# Sheet1.net
KiCad netlist of a schematic drawn in Altium Designer
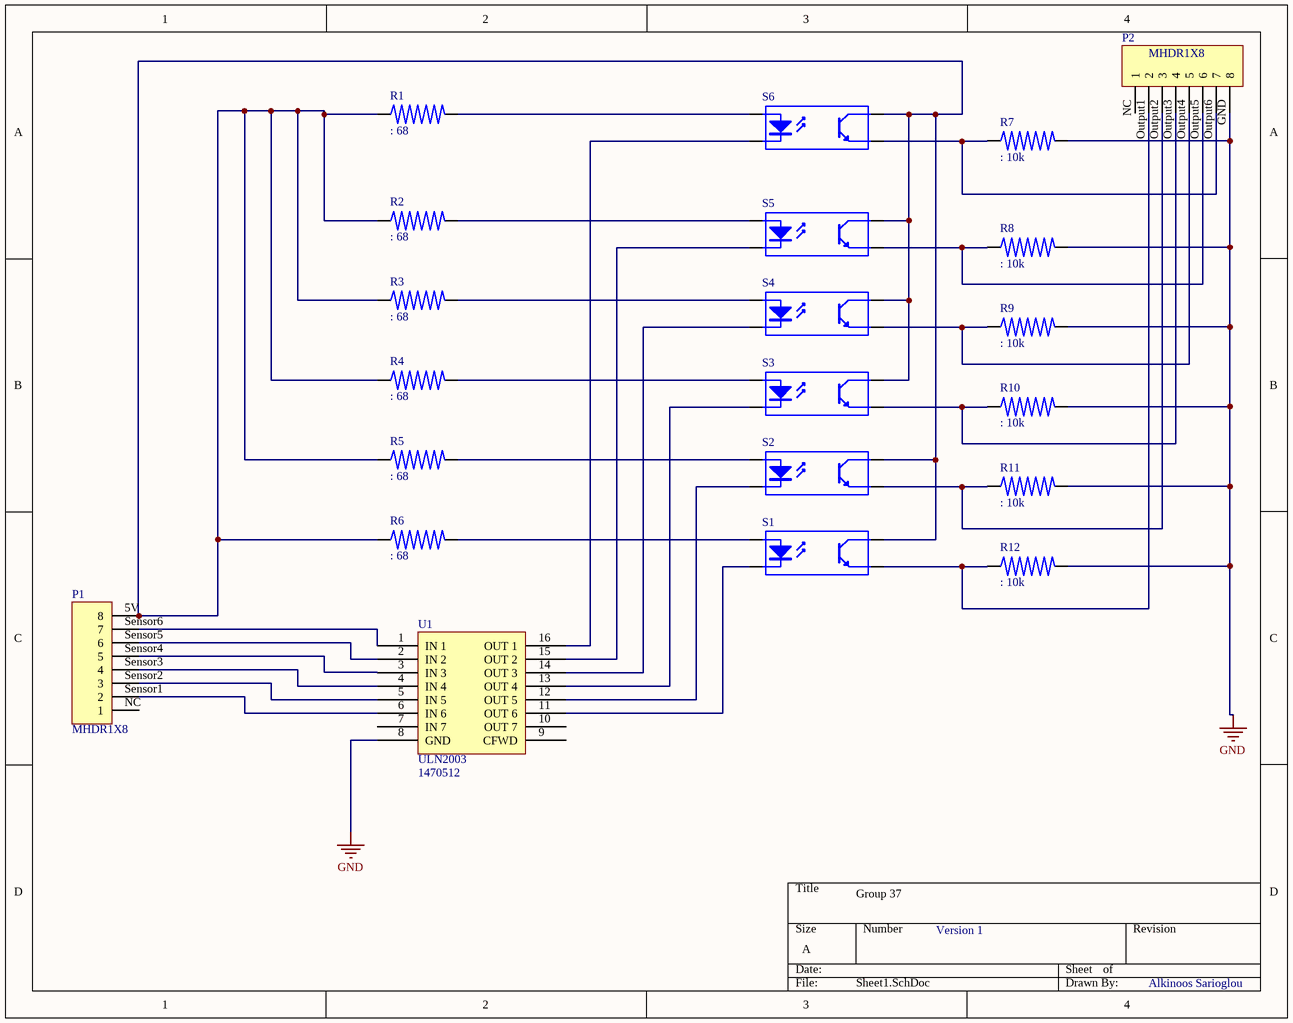
[diagram p0: Sheet1.SchDoc]

(export (version "E")
  (design (tool "Eeschema 10.0.6"))
  (components
    (comp (ref "P1")
      (value "MHDR1X8")
      (footprint "MHDR1X8")
      (description "Header, 8-Pin")
      (fields (field (name "PUBLISHER") "Altium Limited"))
      (libsource (lib "") (part "MHDR1X8_1"))
    )
    (comp (ref "P2")
      (value "MHDR1X8")
      (footprint "MHDR1X8")
      (description "Header, 8-Pin")
      (fields (field (name "PUBLISHER") "Altium Limited"))
      (libsource (lib "Miscellaneous Connectors") (part "MHDR1X8"))
    )
    (comp (ref "R1")
      (value "Resistor (IO board)")
      (footprint "RESISTOR_10K_TH_QW")
      (description "Resistor (SFR25)")
      (fields (field (name "ALTIUM_UNNAMED_1") "68"))
      (libsource (lib "Integrated_Library") (part "Resistor(IO board)"))
    )
    (comp (ref "R2")
      (value "Resistor (IO board)")
      (footprint "RESISTOR_10K_TH_QW")
      (description "Resistor (SFR25)")
      (fields (field (name "ALTIUM_UNNAMED_1") "68"))
      (libsource (lib "Integrated_Library") (part "Resistor(IO board)"))
    )
    (comp (ref "R3")
      (value "Resistor (IO board)")
      (footprint "RESISTOR_10K_TH_QW")
      (description "Resistor (SFR25)")
      (fields (field (name "ALTIUM_UNNAMED_1") "68"))
      (libsource (lib "Integrated_Library") (part "Resistor(IO board)"))
    )
    (comp (ref "R4")
      (value "Resistor (IO board)")
      (footprint "RESISTOR_10K_TH_QW")
      (description "Resistor (SFR25)")
      (fields (field (name "ALTIUM_UNNAMED_1") "68"))
      (libsource (lib "Integrated_Library") (part "Resistor(IO board)"))
    )
    (comp (ref "R5")
      (value "Resistor (IO board)")
      (footprint "RESISTOR_10K_TH_QW")
      (description "Resistor (SFR25)")
      (fields (field (name "ALTIUM_UNNAMED_1") "68"))
      (libsource (lib "Integrated_Library") (part "Resistor(IO board)"))
    )
    (comp (ref "R6")
      (value "Resistor (IO board)")
      (footprint "RESISTOR_10K_TH_QW")
      (description "Resistor (SFR25)")
      (fields (field (name "ALTIUM_UNNAMED_1") "68"))
      (libsource (lib "Integrated_Library") (part "Resistor(IO board)"))
    )
    (comp (ref "R7")
      (value "Resistor (IO board)")
      (footprint "RESISTOR_10K_TH_QW")
      (description "Resistor (SFR25)")
      (fields (field (name "ALTIUM_UNNAMED_1") "10k"))
      (libsource (lib "Integrated_Library") (part "Resistor(IO board)"))
    )
    (comp (ref "R8")
      (value "Resistor (IO board)")
      (footprint "RESISTOR_10K_TH_QW")
      (description "Resistor (SFR25)")
      (fields (field (name "ALTIUM_UNNAMED_1") "10k"))
      (libsource (lib "Integrated_Library") (part "Resistor(IO board)"))
    )
    (comp (ref "R9")
      (value "Resistor (IO board)")
      (footprint "RESISTOR_10K_TH_QW")
      (description "Resistor (SFR25)")
      (fields (field (name "ALTIUM_UNNAMED_1") "10k"))
      (libsource (lib "Integrated_Library") (part "Resistor(IO board)"))
    )
    (comp (ref "R10")
      (value "Resistor (IO board)")
      (footprint "RESISTOR_10K_TH_QW")
      (description "Resistor (SFR25)")
      (fields (field (name "ALTIUM_UNNAMED_1") "10k"))
      (libsource (lib "Integrated_Library") (part "Resistor(IO board)"))
    )
    (comp (ref "R11")
      (value "Resistor (IO board)")
      (footprint "RESISTOR_10K_TH_QW")
      (description "Resistor (SFR25)")
      (fields (field (name "ALTIUM_UNNAMED_1") "10k"))
      (libsource (lib "Integrated_Library") (part "Resistor(IO board)"))
    )
    (comp (ref "R12")
      (value "Resistor (IO board)")
      (footprint "RESISTOR_10K_TH_QW")
      (description "Resistor (SFR25)")
      (fields (field (name "ALTIUM_UNNAMED_1") "10k"))
      (libsource (lib "Integrated_Library") (part "Resistor(IO board)"))
    )
    (comp (ref "S1")
      (value "TCRT5000(On PCB)")
      (footprint "TCRT5000 Breakout")
      (description "4-Pin Phototransistor Optocoupler")
      (fields (field (name "PUBLISHER") "Altium Limited"))
      (libsource (lib "Integrated_Library") (part "TCRT5000(On PCB)"))
    )
    (comp (ref "S2")
      (value "TCRT5000(On PCB)")
      (footprint "TCRT5000 Breakout")
      (description "4-Pin Phototransistor Optocoupler")
      (fields (field (name "PUBLISHER") "Altium Limited"))
      (libsource (lib "Integrated_Library") (part "TCRT5000(On PCB)"))
    )
    (comp (ref "S3")
      (value "TCRT5000(On PCB)")
      (footprint "TCRT5000 Breakout")
      (description "4-Pin Phototransistor Optocoupler")
      (fields (field (name "PUBLISHER") "Altium Limited"))
      (libsource (lib "Integrated_Library") (part "TCRT5000(On PCB)"))
    )
    (comp (ref "S4")
      (value "TCRT5000(On PCB)")
      (footprint "TCRT5000 Breakout")
      (description "4-Pin Phototransistor Optocoupler")
      (fields (field (name "PUBLISHER") "Altium Limited"))
      (libsource (lib "Integrated_Library") (part "TCRT5000(On PCB)"))
    )
    (comp (ref "S5")
      (value "TCRT5000(On PCB)")
      (footprint "TCRT5000 Breakout")
      (description "4-Pin Phototransistor Optocoupler")
      (fields (field (name "PUBLISHER") "Altium Limited"))
      (libsource (lib "Integrated_Library") (part "TCRT5000(On PCB)"))
    )
    (comp (ref "S6")
      (value "TCRT5000(On PCB)")
      (footprint "TCRT5000 Breakout")
      (description "4-Pin Phototransistor Optocoupler")
      (fields (field (name "PUBLISHER") "Altium Limited"))
      (libsource (lib "Integrated_Library") (part "TCRT5000(On PCB)"))
    )
    (comp (ref "U1")
      (value "ULN2003")
      (footprint "DILP-16(300) - 3D")
      (description "Darlington Transistor Array")
      (fields (field (name "SUPPLIER PART NUMBER 1") "1470512"))
      (libsource (lib "Integrated_Library") (part "ULN2003"))
    )
  )
  (nets
    (net (code "1") (name "GND") (class "Default")
      (node (ref "P2") (pin "GND") (pinfunction "8_GND") (pintype "passive"))
      (node (ref "R10") (pin "2") (pinfunction "2_2") (pintype "passive"))
      (node (ref "R11") (pin "2") (pinfunction "2_2") (pintype "passive"))
      (node (ref "R12") (pin "2") (pinfunction "2_2") (pintype "passive"))
      (node (ref "R7") (pin "2") (pinfunction "2_2") (pintype "passive"))
      (node (ref "R8") (pin "2") (pinfunction "2_2") (pintype "passive"))
      (node (ref "R9") (pin "2") (pinfunction "2_2") (pintype "passive"))
      (node (ref "U1") (pin "8") (pinfunction "GND_8") (pintype "passive"))
    )
    (net (code "2") (name "Net-(P1-2)") (class "Default")
      (node (ref "P1") (pin "Sensor1") (pinfunction "2_Sensor1") (pintype "passive"))
      (node (ref "U1") (pin "6") (pinfunction "IN_6_6") (pintype "passive"))
    )
    (net (code "3") (name "Net-(P1-3)") (class "Default")
      (node (ref "P1") (pin "Sensor2") (pinfunction "3_Sensor2") (pintype "passive"))
      (node (ref "U1") (pin "5") (pinfunction "IN_5_5") (pintype "passive"))
    )
    (net (code "4") (name "Net-(P1-4)") (class "Default")
      (node (ref "P1") (pin "Sensor3") (pinfunction "4_Sensor3") (pintype "passive"))
      (node (ref "U1") (pin "4") (pinfunction "IN_4_4") (pintype "passive"))
    )
    (net (code "5") (name "Net-(P1-5)") (class "Default")
      (node (ref "P1") (pin "Sensor4") (pinfunction "5_Sensor4") (pintype "passive"))
      (node (ref "U1") (pin "3") (pinfunction "IN_3_3") (pintype "passive"))
    )
    (net (code "6") (name "Net-(P1-6)") (class "Default")
      (node (ref "P1") (pin "Sensor5") (pinfunction "6_Sensor5") (pintype "passive"))
      (node (ref "U1") (pin "2") (pinfunction "IN_2_2") (pintype "passive"))
    )
    (net (code "7") (name "Net-(P1-7)") (class "Default")
      (node (ref "P1") (pin "Sensor6") (pinfunction "7_Sensor6") (pintype "passive"))
      (node (ref "U1") (pin "1") (pinfunction "IN_1_1") (pintype "passive"))
    )
    (net (code "8") (name "Net-(P1-8)") (class "Default")
      (node (ref "P1") (pin "5V") (pinfunction "8_5V") (pintype "passive"))
      (node (ref "R1") (pin "1") (pinfunction "1_1") (pintype "passive"))
      (node (ref "R2") (pin "1") (pinfunction "1_1") (pintype "passive"))
      (node (ref "R3") (pin "1") (pinfunction "1_1") (pintype "passive"))
      (node (ref "R4") (pin "1") (pinfunction "1_1") (pintype "passive"))
      (node (ref "R5") (pin "1") (pinfunction "1_1") (pintype "passive"))
      (node (ref "R6") (pin "1") (pinfunction "1_1") (pintype "passive"))
      (node (ref "S1") (pin "4") (pinfunction "C_4") (pintype "passive"))
      (node (ref "S2") (pin "4") (pinfunction "C_4") (pintype "passive"))
      (node (ref "S3") (pin "4") (pinfunction "C_4") (pintype "passive"))
      (node (ref "S4") (pin "4") (pinfunction "C_4") (pintype "passive"))
      (node (ref "S5") (pin "4") (pinfunction "C_4") (pintype "passive"))
      (node (ref "S6") (pin "4") (pinfunction "C_4") (pintype "passive"))
    )
    (net (code "9") (name "Net-(P2-2)") (class "Default")
      (node (ref "P2") (pin "Output1") (pinfunction "2_Output1") (pintype "passive"))
      (node (ref "R12") (pin "1") (pinfunction "1_1") (pintype "passive"))
      (node (ref "S1") (pin "3") (pinfunction "E_3") (pintype "passive"))
    )
    (net (code "10") (name "Net-(P2-3)") (class "Default")
      (node (ref "P2") (pin "Output2") (pinfunction "3_Output2") (pintype "passive"))
      (node (ref "R11") (pin "1") (pinfunction "1_1") (pintype "passive"))
      (node (ref "S2") (pin "3") (pinfunction "E_3") (pintype "passive"))
    )
    (net (code "11") (name "Net-(P2-4)") (class "Default")
      (node (ref "P2") (pin "Output3") (pinfunction "4_Output3") (pintype "passive"))
      (node (ref "R10") (pin "1") (pinfunction "1_1") (pintype "passive"))
      (node (ref "S3") (pin "3") (pinfunction "E_3") (pintype "passive"))
    )
    (net (code "12") (name "Net-(P2-5)") (class "Default")
      (node (ref "P2") (pin "Output4") (pinfunction "5_Output4") (pintype "passive"))
      (node (ref "R9") (pin "1") (pinfunction "1_1") (pintype "passive"))
      (node (ref "S4") (pin "3") (pinfunction "E_3") (pintype "passive"))
    )
    (net (code "13") (name "Net-(P2-6)") (class "Default")
      (node (ref "P2") (pin "Output5") (pinfunction "6_Output5") (pintype "passive"))
      (node (ref "R8") (pin "1") (pinfunction "1_1") (pintype "passive"))
      (node (ref "S5") (pin "3") (pinfunction "E_3") (pintype "passive"))
    )
    (net (code "14") (name "Net-(P2-7)") (class "Default")
      (node (ref "P2") (pin "Output6") (pinfunction "7_Output6") (pintype "passive"))
      (node (ref "R7") (pin "1") (pinfunction "1_1") (pintype "passive"))
      (node (ref "S6") (pin "3") (pinfunction "E_3") (pintype "passive"))
    )
    (net (code "15") (name "Net-(S1-A)") (class "Default")
      (node (ref "R6") (pin "2") (pinfunction "2_2") (pintype "passive"))
      (node (ref "S1") (pin "1") (pinfunction "A_1") (pintype "passive"))
    )
    (net (code "16") (name "Net-(S1-K)") (class "Default")
      (node (ref "S1") (pin "2") (pinfunction "K_2") (pintype "passive"))
      (node (ref "U1") (pin "11") (pinfunction "OUT_6_11") (pintype "passive"))
    )
    (net (code "17") (name "Net-(S2-A)") (class "Default")
      (node (ref "R5") (pin "2") (pinfunction "2_2") (pintype "passive"))
      (node (ref "S2") (pin "1") (pinfunction "A_1") (pintype "passive"))
    )
    (net (code "18") (name "Net-(S2-K)") (class "Default")
      (node (ref "S2") (pin "2") (pinfunction "K_2") (pintype "passive"))
      (node (ref "U1") (pin "12") (pinfunction "OUT_5_12") (pintype "passive"))
    )
    (net (code "19") (name "Net-(S3-A)") (class "Default")
      (node (ref "R4") (pin "2") (pinfunction "2_2") (pintype "passive"))
      (node (ref "S3") (pin "1") (pinfunction "A_1") (pintype "passive"))
    )
    (net (code "20") (name "Net-(S3-K)") (class "Default")
      (node (ref "S3") (pin "2") (pinfunction "K_2") (pintype "passive"))
      (node (ref "U1") (pin "13") (pinfunction "OUT_4_13") (pintype "passive"))
    )
    (net (code "21") (name "Net-(S4-A)") (class "Default")
      (node (ref "R3") (pin "2") (pinfunction "2_2") (pintype "passive"))
      (node (ref "S4") (pin "1") (pinfunction "A_1") (pintype "passive"))
    )
    (net (code "22") (name "Net-(S4-K)") (class "Default")
      (node (ref "S4") (pin "2") (pinfunction "K_2") (pintype "passive"))
      (node (ref "U1") (pin "14") (pinfunction "OUT_3_14") (pintype "passive"))
    )
    (net (code "23") (name "Net-(S5-A)") (class "Default")
      (node (ref "R2") (pin "2") (pinfunction "2_2") (pintype "passive"))
      (node (ref "S5") (pin "1") (pinfunction "A_1") (pintype "passive"))
    )
    (net (code "24") (name "Net-(S5-K)") (class "Default")
      (node (ref "S5") (pin "2") (pinfunction "K_2") (pintype "passive"))
      (node (ref "U1") (pin "15") (pinfunction "OUT_2_15") (pintype "passive"))
    )
    (net (code "25") (name "Net-(S6-A)") (class "Default")
      (node (ref "R1") (pin "2") (pinfunction "2_2") (pintype "passive"))
      (node (ref "S6") (pin "1") (pinfunction "A_1") (pintype "passive"))
    )
    (net (code "26") (name "Net-(S6-K)") (class "Default")
      (node (ref "S6") (pin "2") (pinfunction "K_2") (pintype "passive"))
      (node (ref "U1") (pin "16") (pinfunction "OUT_1_16") (pintype "passive"))
    )
    (net (code "27") (name "unconnected-(P1-1-PadNC)") (class "Default")
      (node (ref "P1") (pin "NC") (pinfunction "1_NC") (pintype "passive"))
    )
    (net (code "28") (name "unconnected-(P2-1-PadNC)") (class "Default")
      (node (ref "P2") (pin "NC") (pinfunction "1_NC") (pintype "passive"))
    )
    (net (code "29") (name "unconnected-(U1-CFWD-Pad9)") (class "Default")
      (node (ref "U1") (pin "9") (pinfunction "CFWD_9") (pintype "passive"))
    )
    (net (code "30") (name "unconnected-(U1-IN_7-Pad7)") (class "Default")
      (node (ref "U1") (pin "7") (pinfunction "IN_7_7") (pintype "passive"))
    )
    (net (code "31") (name "unconnected-(U1-OUT_7-Pad10)") (class "Default")
      (node (ref "U1") (pin "10") (pinfunction "OUT_7_10") (pintype "passive"))
    )
  )
)
